# NCS_Wireless_Control_Card_hc12_display_c.net
KiCad netlist of a schematic drawn in Altium Designer
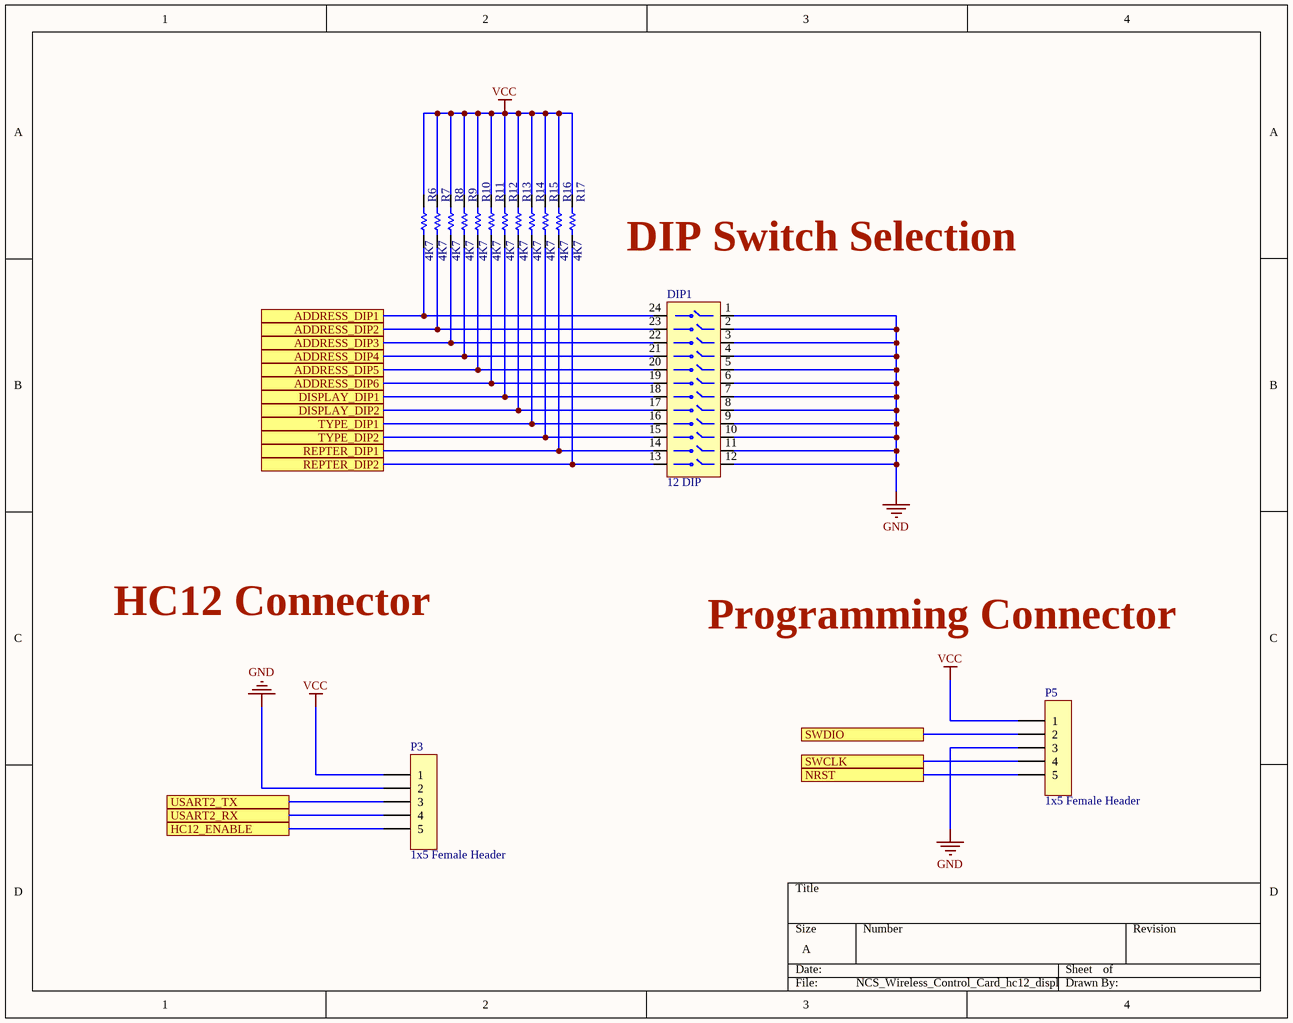
[diagram p0: NCS_Wireless_Control_Card_hc12_display_conn.SchDoc]

(export (version "E")
  (design (tool "Eeschema 10.0.6"))
  (components
    (comp (ref "DIP1")
      (value "12 DIP")
      (footprint "DIP24")
      (libsource (lib "NCS_Wireless_Bed_Unit") (part "12 Way 2.54MM DIP switch - SUNROM"))
    )
    (comp (ref "P3")
      (value "1x5 Female Header")
      (footprint "1x5 Female Header")
      (description "2.54mm (0.1) Pitch SIL Vertical PC Tail Pin Header, 6.1mm mating pin height, tin, 5 contacts\"")
      (fields (field (name "MANUFACTURER") "Harwin") (field (name "MANUFACTURER PART NUMBER") "M20-9990546"))
      (libsource (lib "schlib") (part "M20-9990546"))
    )
    (comp (ref "P5")
      (value "1x5 Female Header")
      (footprint "1x5 Female Header")
      (description "2.54mm (0.1) Pitch SIL Vertical PC Tail Pin Header, 6.1mm mating pin height, tin, 5 contacts\"")
      (fields (field (name "MANUFACTURER") "Harwin") (field (name "MANUFACTURER PART NUMBER") "M20-9990546"))
      (libsource (lib "schlib") (part "M20-9990546"))
    )
    (comp (ref "R6")
      (value "4K7")
      (footprint "RC0805FR-7W330RL")
      (description "Res Thick Film 0805 330 Ohm 1% 0.25W(1/4W) ±200ppm/C Pad SMD T/R")
      (fields
        (field (name "MANUFACTURER") "Yageo")
        (field (name "MANUFACTURER PART NUMBER") "RC0805FR-7W330RL")
      )
      (libsource (lib "schlib") (part "RC0805FR-7W330RL"))
    )
    (comp (ref "R7")
      (value "4K7")
      (footprint "RC0805FR-7W330RL")
      (description "Res Thick Film 0805 330 Ohm 1% 0.25W(1/4W) ±200ppm/C Pad SMD T/R")
      (fields
        (field (name "MANUFACTURER") "Yageo")
        (field (name "MANUFACTURER PART NUMBER") "RC0805FR-7W330RL")
      )
      (libsource (lib "schlib") (part "RC0805FR-7W330RL"))
    )
    (comp (ref "R8")
      (value "4K7")
      (footprint "RC0805FR-7W330RL")
      (description "Res Thick Film 0805 330 Ohm 1% 0.25W(1/4W) ±200ppm/C Pad SMD T/R")
      (fields
        (field (name "MANUFACTURER") "Yageo")
        (field (name "MANUFACTURER PART NUMBER") "RC0805FR-7W330RL")
      )
      (libsource (lib "schlib") (part "RC0805FR-7W330RL"))
    )
    (comp (ref "R9")
      (value "4K7")
      (footprint "RC0805FR-7W330RL")
      (description "Res Thick Film 0805 330 Ohm 1% 0.25W(1/4W) ±200ppm/C Pad SMD T/R")
      (fields
        (field (name "MANUFACTURER") "Yageo")
        (field (name "MANUFACTURER PART NUMBER") "RC0805FR-7W330RL")
      )
      (libsource (lib "schlib") (part "RC0805FR-7W330RL"))
    )
    (comp (ref "R10")
      (value "4K7")
      (footprint "RC0805FR-7W330RL")
      (description "Res Thick Film 0805 330 Ohm 1% 0.25W(1/4W) ±200ppm/C Pad SMD T/R")
      (fields
        (field (name "MANUFACTURER") "Yageo")
        (field (name "MANUFACTURER PART NUMBER") "RC0805FR-7W330RL")
      )
      (libsource (lib "schlib") (part "RC0805FR-7W330RL"))
    )
    (comp (ref "R11")
      (value "4K7")
      (footprint "RC0805FR-7W330RL")
      (description "Res Thick Film 0805 330 Ohm 1% 0.25W(1/4W) ±200ppm/C Pad SMD T/R")
      (fields
        (field (name "MANUFACTURER") "Yageo")
        (field (name "MANUFACTURER PART NUMBER") "RC0805FR-7W330RL")
      )
      (libsource (lib "schlib") (part "RC0805FR-7W330RL"))
    )
    (comp (ref "R12")
      (value "4K7")
      (footprint "RC0805FR-7W330RL")
      (description "Res Thick Film 0805 330 Ohm 1% 0.25W(1/4W) ±200ppm/C Pad SMD T/R")
      (fields
        (field (name "MANUFACTURER") "Yageo")
        (field (name "MANUFACTURER PART NUMBER") "RC0805FR-7W330RL")
      )
      (libsource (lib "schlib") (part "RC0805FR-7W330RL"))
    )
    (comp (ref "R13")
      (value "4K7")
      (footprint "RC0805FR-7W330RL")
      (description "Res Thick Film 0805 330 Ohm 1% 0.25W(1/4W) ±200ppm/C Pad SMD T/R")
      (fields
        (field (name "MANUFACTURER") "Yageo")
        (field (name "MANUFACTURER PART NUMBER") "RC0805FR-7W330RL")
      )
      (libsource (lib "schlib") (part "RC0805FR-7W330RL"))
    )
    (comp (ref "R14")
      (value "4K7")
      (footprint "RC0805FR-7W330RL")
      (description "Res Thick Film 0805 330 Ohm 1% 0.25W(1/4W) ±200ppm/C Pad SMD T/R")
      (fields
        (field (name "MANUFACTURER") "Yageo")
        (field (name "MANUFACTURER PART NUMBER") "RC0805FR-7W330RL")
      )
      (libsource (lib "schlib") (part "RC0805FR-7W330RL"))
    )
    (comp (ref "R15")
      (value "4K7")
      (footprint "RC0805FR-7W330RL")
      (description "Res Thick Film 0805 330 Ohm 1% 0.25W(1/4W) ±200ppm/C Pad SMD T/R")
      (fields
        (field (name "MANUFACTURER") "Yageo")
        (field (name "MANUFACTURER PART NUMBER") "RC0805FR-7W330RL")
      )
      (libsource (lib "schlib") (part "RC0805FR-7W330RL"))
    )
    (comp (ref "R16")
      (value "4K7")
      (footprint "RC0805FR-7W330RL")
      (description "Res Thick Film 0805 330 Ohm 1% 0.25W(1/4W) ±200ppm/C Pad SMD T/R")
      (fields
        (field (name "MANUFACTURER") "Yageo")
        (field (name "MANUFACTURER PART NUMBER") "RC0805FR-7W330RL")
      )
      (libsource (lib "schlib") (part "RC0805FR-7W330RL"))
    )
    (comp (ref "R17")
      (value "4K7")
      (footprint "RC0805FR-7W330RL")
      (description "Res Thick Film 0805 330 Ohm 1% 0.25W(1/4W) ±200ppm/C Pad SMD T/R")
      (fields
        (field (name "MANUFACTURER") "Yageo")
        (field (name "MANUFACTURER PART NUMBER") "RC0805FR-7W330RL")
      )
      (libsource (lib "schlib") (part "RC0805FR-7W330RL"))
    )
  )
  (nets
    (net (code "1") (name "/ADDRESS_DIP1") (class "Default")
      (node (ref "DIP1") (pin "24") (pinfunction "24_24") (pintype "passive"))
      (node (ref "R6") (pin "1") (pinfunction "1_1") (pintype "passive"))
    )
    (net (code "2") (name "/ADDRESS_DIP2") (class "Default")
      (node (ref "DIP1") (pin "23") (pinfunction "23_23") (pintype "passive"))
      (node (ref "R7") (pin "1") (pinfunction "1_1") (pintype "passive"))
    )
    (net (code "3") (name "/ADDRESS_DIP3") (class "Default")
      (node (ref "DIP1") (pin "22") (pinfunction "22_22") (pintype "passive"))
      (node (ref "R8") (pin "1") (pinfunction "1_1") (pintype "passive"))
    )
    (net (code "4") (name "/ADDRESS_DIP4") (class "Default")
      (node (ref "DIP1") (pin "21") (pinfunction "21_21") (pintype "passive"))
      (node (ref "R9") (pin "1") (pinfunction "1_1") (pintype "passive"))
    )
    (net (code "5") (name "/ADDRESS_DIP5") (class "Default")
      (node (ref "DIP1") (pin "20") (pinfunction "20_20") (pintype "passive"))
      (node (ref "R10") (pin "1") (pinfunction "1_1") (pintype "passive"))
    )
    (net (code "6") (name "/ADDRESS_DIP6") (class "Default")
      (node (ref "DIP1") (pin "19") (pinfunction "19_19") (pintype "passive"))
      (node (ref "R11") (pin "1") (pinfunction "1_1") (pintype "passive"))
    )
    (net (code "7") (name "/DISPLAY_DIP1") (class "Default")
      (node (ref "DIP1") (pin "18") (pinfunction "18_18") (pintype "passive"))
      (node (ref "R12") (pin "1") (pinfunction "1_1") (pintype "passive"))
    )
    (net (code "8") (name "/DISPLAY_DIP2") (class "Default")
      (node (ref "DIP1") (pin "17") (pinfunction "17_17") (pintype "passive"))
      (node (ref "R13") (pin "1") (pinfunction "1_1") (pintype "passive"))
    )
    (net (code "9") (name "/HC12_ENABLE") (class "Default")
      (node (ref "P3") (pin "5") (pinfunction "5_5") (pintype "passive"))
    )
    (net (code "10") (name "/NRST") (class "Default")
      (node (ref "P5") (pin "5") (pinfunction "5_5") (pintype "passive"))
    )
    (net (code "11") (name "/REPTER_DIP1") (class "Default")
      (node (ref "DIP1") (pin "14") (pinfunction "14_14") (pintype "passive"))
      (node (ref "R16") (pin "1") (pinfunction "1_1") (pintype "passive"))
    )
    (net (code "12") (name "/REPTER_DIP2") (class "Default")
      (node (ref "DIP1") (pin "13") (pinfunction "13_13") (pintype "passive"))
      (node (ref "R17") (pin "1") (pinfunction "1_1") (pintype "passive"))
    )
    (net (code "13") (name "/SWCLK") (class "Default")
      (node (ref "P5") (pin "4") (pinfunction "4_4") (pintype "passive"))
    )
    (net (code "14") (name "/SWDIO") (class "Default")
      (node (ref "P5") (pin "2") (pinfunction "2_2") (pintype "passive"))
    )
    (net (code "15") (name "/TYPE_DIP1") (class "Default")
      (node (ref "DIP1") (pin "16") (pinfunction "16_16") (pintype "passive"))
      (node (ref "R14") (pin "1") (pinfunction "1_1") (pintype "passive"))
    )
    (net (code "16") (name "/TYPE_DIP2") (class "Default")
      (node (ref "DIP1") (pin "15") (pinfunction "15_15") (pintype "passive"))
      (node (ref "R15") (pin "1") (pinfunction "1_1") (pintype "passive"))
    )
    (net (code "17") (name "/USART2_RX") (class "Default")
      (node (ref "P3") (pin "4") (pinfunction "4_4") (pintype "passive"))
    )
    (net (code "18") (name "/USART2_TX") (class "Default")
      (node (ref "P3") (pin "3") (pinfunction "3_3") (pintype "passive"))
    )
    (net (code "19") (name "GND") (class "Default")
      (node (ref "DIP1") (pin "1") (pinfunction "1_1") (pintype "passive"))
      (node (ref "DIP1") (pin "10") (pinfunction "10_10") (pintype "passive"))
      (node (ref "DIP1") (pin "11") (pinfunction "11_11") (pintype "passive"))
      (node (ref "DIP1") (pin "12") (pinfunction "12_12") (pintype "passive"))
      (node (ref "DIP1") (pin "2") (pinfunction "2_2") (pintype "passive"))
      (node (ref "DIP1") (pin "3") (pinfunction "3_3") (pintype "passive"))
      (node (ref "DIP1") (pin "4") (pinfunction "4_4") (pintype "passive"))
      (node (ref "DIP1") (pin "5") (pinfunction "5_5") (pintype "passive"))
      (node (ref "DIP1") (pin "6") (pinfunction "6_6") (pintype "passive"))
      (node (ref "DIP1") (pin "7") (pinfunction "7_7") (pintype "passive"))
      (node (ref "DIP1") (pin "8") (pinfunction "8_8") (pintype "passive"))
      (node (ref "DIP1") (pin "9") (pinfunction "9_9") (pintype "passive"))
      (node (ref "P3") (pin "2") (pinfunction "2_2") (pintype "passive"))
      (node (ref "P5") (pin "3") (pinfunction "3_3") (pintype "passive"))
    )
    (net (code "20") (name "VCC") (class "Default")
      (node (ref "P3") (pin "1") (pinfunction "1_1") (pintype "passive"))
      (node (ref "P5") (pin "1") (pinfunction "1_1") (pintype "passive"))
      (node (ref "R10") (pin "2") (pinfunction "2_2") (pintype "passive"))
      (node (ref "R11") (pin "2") (pinfunction "2_2") (pintype "passive"))
      (node (ref "R12") (pin "2") (pinfunction "2_2") (pintype "passive"))
      (node (ref "R13") (pin "2") (pinfunction "2_2") (pintype "passive"))
      (node (ref "R14") (pin "2") (pinfunction "2_2") (pintype "passive"))
      (node (ref "R15") (pin "2") (pinfunction "2_2") (pintype "passive"))
      (node (ref "R16") (pin "2") (pinfunction "2_2") (pintype "passive"))
      (node (ref "R17") (pin "2") (pinfunction "2_2") (pintype "passive"))
      (node (ref "R6") (pin "2") (pinfunction "2_2") (pintype "passive"))
      (node (ref "R7") (pin "2") (pinfunction "2_2") (pintype "passive"))
      (node (ref "R8") (pin "2") (pinfunction "2_2") (pintype "passive"))
      (node (ref "R9") (pin "2") (pinfunction "2_2") (pintype "passive"))
    )
  )
)
